# as14120_x31_fpga_cypress.net
KiCad netlist of a schematic drawn in Altium Designer
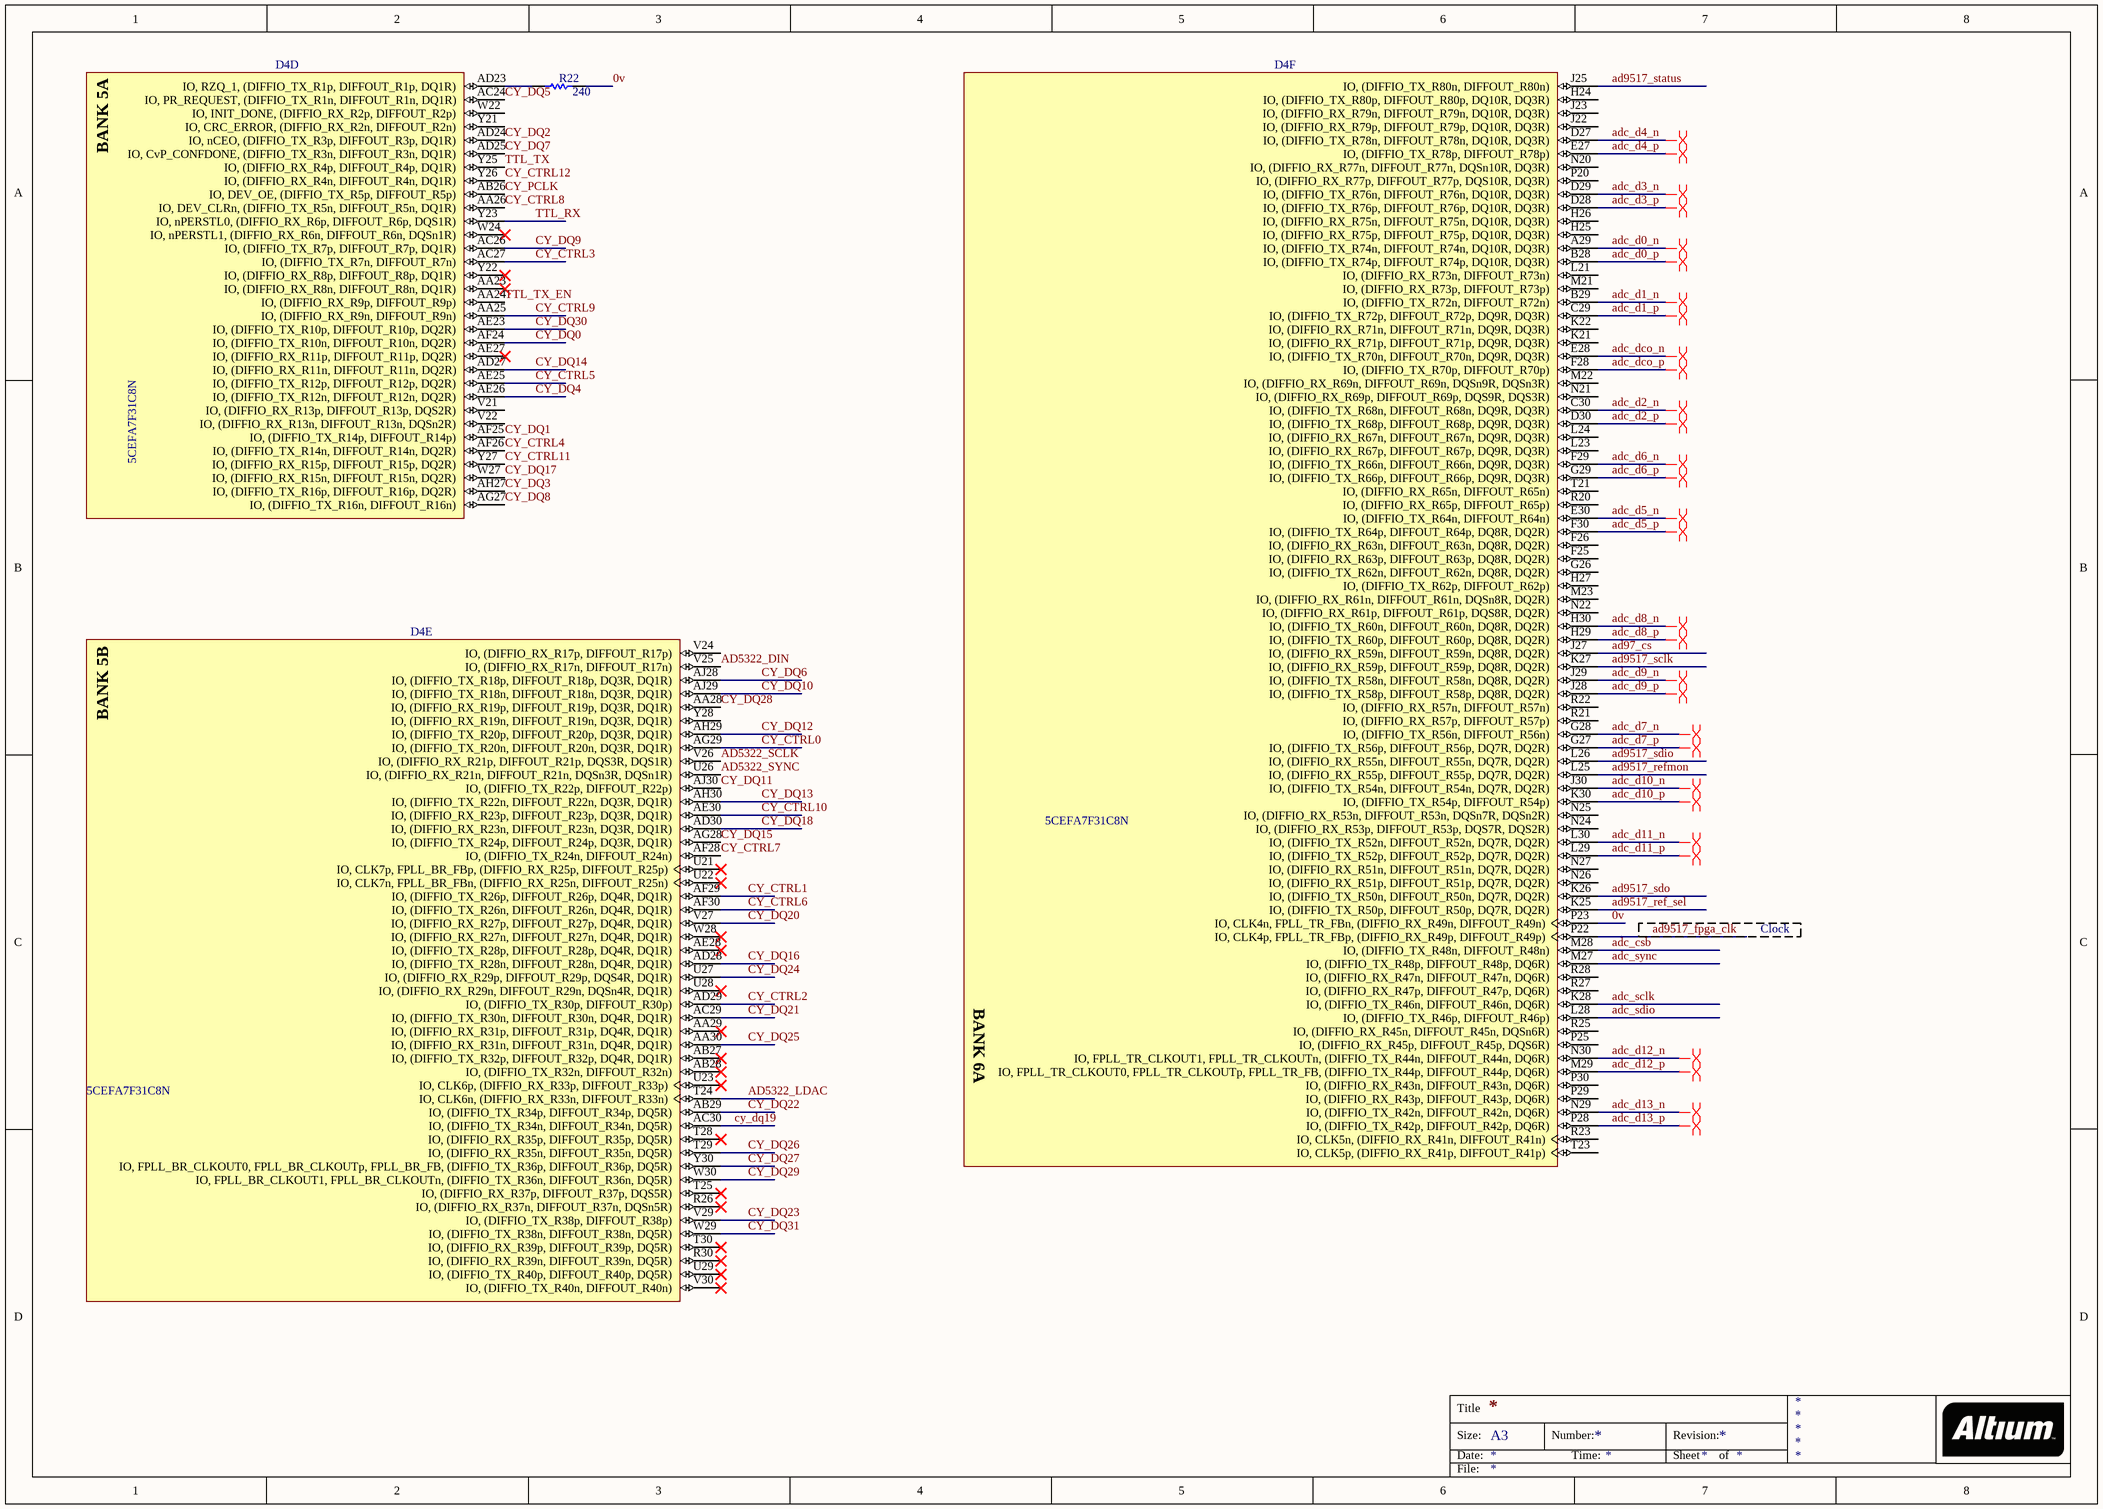
[diagram p0: as14120_x31_fpga_cypress.SchDoc]

(export (version "E")
  (design (tool "Eeschema 10.0.6"))
  (components
    (comp (ref "D4")
      (value "5CEFA7F31C8N")
      (footprint "ALTR-896-FBGA-2000A")
      (fields (field (name "MANUFACTURER") "Altera"))
      (libsource (lib "Altera Cyclone V E") (part "5CEFA7F31C8N"))
    )
    (comp (ref "R22")
      (value "240")
      (footprint "RESC0603(1608)_L")
      (description "1K 0.1W 5% 0603 (1608 Metric)  SMD")
      (fields (field (name "TOLERANCE") "5 %") (field (name "POWER") "0.1 W"))
      (libsource (lib "as14120") (part "RES_0603"))
    )
  )
  (nets
    (net (code "1") (name "/0v") (class "Default")
      (node (ref "D4") (pin "P23") (pinfunction "IO,_CLK4n,_FPLL_TR_FBn,_(DIFFIO_RX_R49n,_DIFFOUT_R49n)_P23") (pintype "bidirectional"))
      (node (ref "R22") (pin "2") (pinfunction "2_2") (pintype "passive"))
    )
    (net (code "2") (name "/AD5322_DIN") (class "Default")
      (node (ref "D4") (pin "V25") (pinfunction "IO,_(DIFFIO_RX_R17n,_DIFFOUT_R17n)_V25") (pintype "bidirectional"))
    )
    (net (code "3") (name "/AD5322_LDAC") (class "Default")
      (node (ref "D4") (pin "T24") (pinfunction "IO,_CLK6n,_(DIFFIO_RX_R33n,_DIFFOUT_R33n)_T24") (pintype "bidirectional"))
    )
    (net (code "4") (name "/AD5322_SCLK") (class "Default")
      (node (ref "D4") (pin "V26") (pinfunction "IO,_(DIFFIO_RX_R21p,_DIFFOUT_R21p,_DQS3R,_DQS1R)_V26") (pintype "bidirectional"))
    )
    (net (code "5") (name "/AD5322_SYNC") (class "Default")
      (node (ref "D4") (pin "U26") (pinfunction "IO,_(DIFFIO_RX_R21n,_DIFFOUT_R21n,_DQSn3R,_DQSn1R)_U26") (pintype "bidirectional"))
    )
    (net (code "6") (name "/CY_CTRL0") (class "Default")
      (node (ref "D4") (pin "AG29") (pinfunction "IO,_(DIFFIO_TX_R20n,_DIFFOUT_R20n,_DQ3R,_DQ1R)_AG29") (pintype "bidirectional"))
    )
    (net (code "7") (name "/CY_CTRL1") (class "Default")
      (node (ref "D4") (pin "AF29") (pinfunction "IO,_(DIFFIO_TX_R26p,_DIFFOUT_R26p,_DQ4R,_DQ1R)_AF29") (pintype "bidirectional"))
    )
    (net (code "8") (name "/CY_CTRL2") (class "Default")
      (node (ref "D4") (pin "AD29") (pinfunction "IO,_(DIFFIO_TX_R30p,_DIFFOUT_R30p)_AD29") (pintype "bidirectional"))
    )
    (net (code "9") (name "/CY_CTRL3") (class "Default")
      (node (ref "D4") (pin "AC27") (pinfunction "IO,_(DIFFIO_TX_R7n,_DIFFOUT_R7n)_AC27") (pintype "bidirectional"))
    )
    (net (code "10") (name "/CY_CTRL4") (class "Default")
      (node (ref "D4") (pin "AF26") (pinfunction "IO,_(DIFFIO_TX_R14n,_DIFFOUT_R14n,_DQ2R)_AF26") (pintype "bidirectional"))
    )
    (net (code "11") (name "/CY_CTRL5") (class "Default")
      (node (ref "D4") (pin "AE25") (pinfunction "IO,_(DIFFIO_TX_R12p,_DIFFOUT_R12p,_DQ2R)_AE25") (pintype "bidirectional"))
    )
    (net (code "12") (name "/CY_CTRL6") (class "Default")
      (node (ref "D4") (pin "AF30") (pinfunction "IO,_(DIFFIO_TX_R26n,_DIFFOUT_R26n,_DQ4R,_DQ1R)_AF30") (pintype "bidirectional"))
    )
    (net (code "13") (name "/CY_CTRL7") (class "Default")
      (node (ref "D4") (pin "AF28") (pinfunction "IO,_(DIFFIO_TX_R24n,_DIFFOUT_R24n)_AF28") (pintype "bidirectional"))
    )
    (net (code "14") (name "/CY_CTRL8") (class "Default")
      (node (ref "D4") (pin "AA26") (pinfunction "IO,_DEV_CLRn,_(DIFFIO_TX_R5n,_DIFFOUT_R5n,_DQ1R)_AA26") (pintype "bidirectional"))
    )
    (net (code "15") (name "/CY_CTRL9") (class "Default")
      (node (ref "D4") (pin "AA25") (pinfunction "IO,_(DIFFIO_RX_R9n,_DIFFOUT_R9n)_AA25") (pintype "bidirectional"))
    )
    (net (code "16") (name "/CY_CTRL10") (class "Default")
      (node (ref "D4") (pin "AE30") (pinfunction "IO,_(DIFFIO_RX_R23p,_DIFFOUT_R23p,_DQ3R,_DQ1R)_AE30") (pintype "bidirectional"))
    )
    (net (code "17") (name "/CY_CTRL11") (class "Default")
      (node (ref "D4") (pin "Y27") (pinfunction "IO,_(DIFFIO_RX_R15p,_DIFFOUT_R15p,_DQ2R)_Y27") (pintype "bidirectional"))
    )
    (net (code "18") (name "/CY_CTRL12") (class "Default")
      (node (ref "D4") (pin "Y26") (pinfunction "IO,_(DIFFIO_RX_R4n,_DIFFOUT_R4n,_DQ1R)_Y26") (pintype "bidirectional"))
    )
    (net (code "19") (name "/CY_DQ0") (class "Default")
      (node (ref "D4") (pin "AF24") (pinfunction "IO,_(DIFFIO_TX_R10n,_DIFFOUT_R10n,_DQ2R)_AF24") (pintype "bidirectional"))
    )
    (net (code "20") (name "/CY_DQ1") (class "Default")
      (node (ref "D4") (pin "AF25") (pinfunction "IO,_(DIFFIO_TX_R14p,_DIFFOUT_R14p)_AF25") (pintype "bidirectional"))
    )
    (net (code "21") (name "/CY_DQ2") (class "Default")
      (node (ref "D4") (pin "AD24") (pinfunction "IO,_nCEO,_(DIFFIO_TX_R3p,_DIFFOUT_R3p,_DQ1R)_AD24") (pintype "bidirectional"))
    )
    (net (code "22") (name "/CY_DQ3") (class "Default")
      (node (ref "D4") (pin "AH27") (pinfunction "IO,_(DIFFIO_TX_R16p,_DIFFOUT_R16p,_DQ2R)_AH27") (pintype "bidirectional"))
    )
    (net (code "23") (name "/CY_DQ4") (class "Default")
      (node (ref "D4") (pin "AE26") (pinfunction "IO,_(DIFFIO_TX_R12n,_DIFFOUT_R12n,_DQ2R)_AE26") (pintype "bidirectional"))
    )
    (net (code "24") (name "/CY_DQ5") (class "Default")
      (node (ref "D4") (pin "AC24") (pinfunction "IO,_PR_REQUEST,_(DIFFIO_TX_R1n,_DIFFOUT_R1n,_DQ1R)_AC24") (pintype "bidirectional"))
    )
    (net (code "25") (name "/CY_DQ6") (class "Default")
      (node (ref "D4") (pin "AJ28") (pinfunction "IO,_(DIFFIO_TX_R18p,_DIFFOUT_R18p,_DQ3R,_DQ1R)_AJ28") (pintype "bidirectional"))
    )
    (net (code "26") (name "/CY_DQ7") (class "Default")
      (node (ref "D4") (pin "AD25") (pinfunction "IO,_CvP_CONFDONE,_(DIFFIO_TX_R3n,_DIFFOUT_R3n,_DQ1R)_AD25") (pintype "bidirectional"))
    )
    (net (code "27") (name "/CY_DQ8") (class "Default")
      (node (ref "D4") (pin "AG27") (pinfunction "IO,_(DIFFIO_TX_R16n,_DIFFOUT_R16n)_AG27") (pintype "bidirectional"))
    )
    (net (code "28") (name "/CY_DQ9") (class "Default")
      (node (ref "D4") (pin "AC26") (pinfunction "IO,_(DIFFIO_TX_R7p,_DIFFOUT_R7p,_DQ1R)_AC26") (pintype "bidirectional"))
    )
    (net (code "29") (name "/CY_DQ10") (class "Default")
      (node (ref "D4") (pin "AJ29") (pinfunction "IO,_(DIFFIO_TX_R18n,_DIFFOUT_R18n,_DQ3R,_DQ1R)_AJ29") (pintype "bidirectional"))
    )
    (net (code "30") (name "/CY_DQ11") (class "Default")
      (node (ref "D4") (pin "AJ30") (pinfunction "IO,_(DIFFIO_TX_R22p,_DIFFOUT_R22p)_AJ30") (pintype "bidirectional"))
    )
    (net (code "31") (name "/CY_DQ12") (class "Default")
      (node (ref "D4") (pin "AH29") (pinfunction "IO,_(DIFFIO_TX_R20p,_DIFFOUT_R20p,_DQ3R,_DQ1R)_AH29") (pintype "bidirectional"))
    )
    (net (code "32") (name "/CY_DQ13") (class "Default")
      (node (ref "D4") (pin "AH30") (pinfunction "IO,_(DIFFIO_TX_R22n,_DIFFOUT_R22n,_DQ3R,_DQ1R)_AH30") (pintype "bidirectional"))
    )
    (net (code "33") (name "/CY_DQ14") (class "Default")
      (node (ref "D4") (pin "AD27") (pinfunction "IO,_(DIFFIO_RX_R11n,_DIFFOUT_R11n,_DQ2R)_AD27") (pintype "bidirectional"))
    )
    (net (code "34") (name "/CY_DQ15") (class "Default")
      (node (ref "D4") (pin "AG28") (pinfunction "IO,_(DIFFIO_TX_R24p,_DIFFOUT_R24p,_DQ3R,_DQ1R)_AG28") (pintype "bidirectional"))
    )
    (net (code "35") (name "/CY_DQ16") (class "Default")
      (node (ref "D4") (pin "AD28") (pinfunction "IO,_(DIFFIO_TX_R28n,_DIFFOUT_R28n,_DQ4R,_DQ1R)_AD28") (pintype "bidirectional"))
    )
    (net (code "36") (name "/CY_DQ17") (class "Default")
      (node (ref "D4") (pin "W27") (pinfunction "IO,_(DIFFIO_RX_R15n,_DIFFOUT_R15n,_DQ2R)_W27") (pintype "bidirectional"))
    )
    (net (code "37") (name "/CY_DQ18") (class "Default")
      (node (ref "D4") (pin "AD30") (pinfunction "IO,_(DIFFIO_RX_R23n,_DIFFOUT_R23n,_DQ3R,_DQ1R)_AD30") (pintype "bidirectional"))
    )
    (net (code "38") (name "/CY_DQ20") (class "Default")
      (node (ref "D4") (pin "V27") (pinfunction "IO,_(DIFFIO_RX_R27p,_DIFFOUT_R27p,_DQ4R,_DQ1R)_V27") (pintype "bidirectional"))
    )
    (net (code "39") (name "/CY_DQ21") (class "Default")
      (node (ref "D4") (pin "AC29") (pinfunction "IO,_(DIFFIO_TX_R30n,_DIFFOUT_R30n,_DQ4R,_DQ1R)_AC29") (pintype "bidirectional"))
    )
    (net (code "40") (name "/CY_DQ22") (class "Default")
      (node (ref "D4") (pin "AB29") (pinfunction "IO,_(DIFFIO_TX_R34p,_DIFFOUT_R34p,_DQ5R)_AB29") (pintype "bidirectional"))
    )
    (net (code "41") (name "/CY_DQ23") (class "Default")
      (node (ref "D4") (pin "V29") (pinfunction "IO,_(DIFFIO_TX_R38p,_DIFFOUT_R38p)_V29") (pintype "bidirectional"))
    )
    (net (code "42") (name "/CY_DQ24") (class "Default")
      (node (ref "D4") (pin "U27") (pinfunction "IO,_(DIFFIO_RX_R29p,_DIFFOUT_R29p,_DQS4R,_DQ1R)_U27") (pintype "bidirectional"))
    )
    (net (code "43") (name "/CY_DQ25") (class "Default")
      (node (ref "D4") (pin "AA30") (pinfunction "IO,_(DIFFIO_RX_R31n,_DIFFOUT_R31n,_DQ4R,_DQ1R)_AA30") (pintype "bidirectional"))
    )
    (net (code "44") (name "/CY_DQ26") (class "Default")
      (node (ref "D4") (pin "T29") (pinfunction "IO,_(DIFFIO_RX_R35n,_DIFFOUT_R35n,_DQ5R)_T29") (pintype "bidirectional"))
    )
    (net (code "45") (name "/CY_DQ27") (class "Default")
      (node (ref "D4") (pin "Y30") (pinfunction "IO,_FPLL_BR_CLKOUT0,_FPLL_BR_CLKOUTp,_FPLL_BR_FB,_(DIFFIO_TX_R36p,_DIFFOUT_R36p,_DQ5R)_Y30") (pintype "bidirectional"))
    )
    (net (code "46") (name "/CY_DQ28") (class "Default")
      (node (ref "D4") (pin "AA28") (pinfunction "IO,_(DIFFIO_RX_R19p,_DIFFOUT_R19p,_DQ3R,_DQ1R)_AA28") (pintype "bidirectional"))
    )
    (net (code "47") (name "/CY_DQ29") (class "Default")
      (node (ref "D4") (pin "W30") (pinfunction "IO,_FPLL_BR_CLKOUT1,_FPLL_BR_CLKOUTn,_(DIFFIO_TX_R36n,_DIFFOUT_R36n,_DQ5R)_W30") (pintype "bidirectional"))
    )
    (net (code "48") (name "/CY_DQ30") (class "Default")
      (node (ref "D4") (pin "AE23") (pinfunction "IO,_(DIFFIO_TX_R10p,_DIFFOUT_R10p,_DQ2R)_AE23") (pintype "bidirectional"))
    )
    (net (code "49") (name "/CY_DQ31") (class "Default")
      (node (ref "D4") (pin "W29") (pinfunction "IO,_(DIFFIO_TX_R38n,_DIFFOUT_R38n,_DQ5R)_W29") (pintype "bidirectional"))
    )
    (net (code "50") (name "/CY_PCLK") (class "Default")
      (node (ref "D4") (pin "AB26") (pinfunction "IO,_DEV_OE,_(DIFFIO_TX_R5p,_DIFFOUT_R5p)_AB26") (pintype "bidirectional"))
    )
    (net (code "51") (name "/TTL_RX") (class "Default")
      (node (ref "D4") (pin "Y23") (pinfunction "IO,_nPERSTL0,_(DIFFIO_RX_R6p,_DIFFOUT_R6p,_DQS1R)_Y23") (pintype "bidirectional"))
    )
    (net (code "52") (name "/TTL_TX") (class "Default")
      (node (ref "D4") (pin "Y25") (pinfunction "IO,_(DIFFIO_RX_R4p,_DIFFOUT_R4p,_DQ1R)_Y25") (pintype "bidirectional"))
    )
    (net (code "53") (name "/TTL_TX_EN") (class "Default")
      (node (ref "D4") (pin "AA24") (pinfunction "IO,_(DIFFIO_RX_R9p,_DIFFOUT_R9p)_AA24") (pintype "bidirectional"))
    )
    (net (code "54") (name "/ad97_cs") (class "Default")
      (node (ref "D4") (pin "J27") (pinfunction "IO,_(DIFFIO_RX_R59n,_DIFFOUT_R59n,_DQ8R,_DQ2R)_J27") (pintype "bidirectional"))
    )
    (net (code "55") (name "/ad9517_fpga_clk") (class "Default")
      (node (ref "D4") (pin "P22") (pinfunction "IO,_CLK4p,_FPLL_TR_FBp,_(DIFFIO_RX_R49p,_DIFFOUT_R49p)_P22") (pintype "bidirectional"))
    )
    (net (code "56") (name "/ad9517_ref_sel") (class "Default")
      (node (ref "D4") (pin "K25") (pinfunction "IO,_(DIFFIO_TX_R50p,_DIFFOUT_R50p,_DQ7R,_DQ2R)_K25") (pintype "bidirectional"))
    )
    (net (code "57") (name "/ad9517_refmon") (class "Default")
      (node (ref "D4") (pin "L25") (pinfunction "IO,_(DIFFIO_RX_R55p,_DIFFOUT_R55p,_DQ7R,_DQ2R)_L25") (pintype "bidirectional"))
    )
    (net (code "58") (name "/ad9517_sclk") (class "Default")
      (node (ref "D4") (pin "K27") (pinfunction "IO,_(DIFFIO_RX_R59p,_DIFFOUT_R59p,_DQ8R,_DQ2R)_K27") (pintype "bidirectional"))
    )
    (net (code "59") (name "/ad9517_sdio") (class "Default")
      (node (ref "D4") (pin "L26") (pinfunction "IO,_(DIFFIO_RX_R55n,_DIFFOUT_R55n,_DQ7R,_DQ2R)_L26") (pintype "bidirectional"))
    )
    (net (code "60") (name "/ad9517_sdo") (class "Default")
      (node (ref "D4") (pin "K26") (pinfunction "IO,_(DIFFIO_TX_R50n,_DIFFOUT_R50n,_DQ7R,_DQ2R)_K26") (pintype "bidirectional"))
    )
    (net (code "61") (name "/ad9517_status") (class "Default")
      (node (ref "D4") (pin "J25") (pinfunction "IO,_(DIFFIO_TX_R80n,_DIFFOUT_R80n)_J25") (pintype "bidirectional"))
    )
    (net (code "62") (name "/adc_csb") (class "Default")
      (node (ref "D4") (pin "M28") (pinfunction "IO,_(DIFFIO_TX_R48n,_DIFFOUT_R48n)_M28") (pintype "bidirectional"))
    )
    (net (code "63") (name "/adc_d0_n") (class "Default")
      (node (ref "D4") (pin "A29") (pinfunction "IO,_(DIFFIO_TX_R74n,_DIFFOUT_R74n,_DQ10R,_DQ3R)_A29") (pintype "bidirectional"))
    )
    (net (code "64") (name "/adc_d0_p") (class "Default")
      (node (ref "D4") (pin "B28") (pinfunction "IO,_(DIFFIO_TX_R74p,_DIFFOUT_R74p,_DQ10R,_DQ3R)_B28") (pintype "bidirectional"))
    )
    (net (code "65") (name "/adc_d1_n") (class "Default")
      (node (ref "D4") (pin "B29") (pinfunction "IO,_(DIFFIO_TX_R72n,_DIFFOUT_R72n)_B29") (pintype "bidirectional"))
    )
    (net (code "66") (name "/adc_d1_p") (class "Default")
      (node (ref "D4") (pin "C29") (pinfunction "IO,_(DIFFIO_TX_R72p,_DIFFOUT_R72p,_DQ9R,_DQ3R)_C29") (pintype "bidirectional"))
    )
    (net (code "67") (name "/adc_d2_n") (class "Default")
      (node (ref "D4") (pin "C30") (pinfunction "IO,_(DIFFIO_TX_R68n,_DIFFOUT_R68n,_DQ9R,_DQ3R)_C30") (pintype "bidirectional"))
    )
    (net (code "68") (name "/adc_d2_p") (class "Default")
      (node (ref "D4") (pin "D30") (pinfunction "IO,_(DIFFIO_TX_R68p,_DIFFOUT_R68p,_DQ9R,_DQ3R)_D30") (pintype "bidirectional"))
    )
    (net (code "69") (name "/adc_d3_n") (class "Default")
      (node (ref "D4") (pin "D29") (pinfunction "IO,_(DIFFIO_TX_R76n,_DIFFOUT_R76n,_DQ10R,_DQ3R)_D29") (pintype "bidirectional"))
    )
    (net (code "70") (name "/adc_d3_p") (class "Default")
      (node (ref "D4") (pin "D28") (pinfunction "IO,_(DIFFIO_TX_R76p,_DIFFOUT_R76p,_DQ10R,_DQ3R)_D28") (pintype "bidirectional"))
    )
    (net (code "71") (name "/adc_d4_n") (class "Default")
      (node (ref "D4") (pin "D27") (pinfunction "IO,_(DIFFIO_TX_R78n,_DIFFOUT_R78n,_DQ10R,_DQ3R)_D27") (pintype "bidirectional"))
    )
    (net (code "72") (name "/adc_d4_p") (class "Default")
      (node (ref "D4") (pin "E27") (pinfunction "IO,_(DIFFIO_TX_R78p,_DIFFOUT_R78p)_E27") (pintype "bidirectional"))
    )
    (net (code "73") (name "/adc_d5_n") (class "Default")
      (node (ref "D4") (pin "E30") (pinfunction "IO,_(DIFFIO_TX_R64n,_DIFFOUT_R64n)_E30") (pintype "bidirectional"))
    )
    (net (code "74") (name "/adc_d5_p") (class "Default")
      (node (ref "D4") (pin "F30") (pinfunction "IO,_(DIFFIO_TX_R64p,_DIFFOUT_R64p,_DQ8R,_DQ2R)_F30") (pintype "bidirectional"))
    )
    (net (code "75") (name "/adc_d6_n") (class "Default")
      (node (ref "D4") (pin "F29") (pinfunction "IO,_(DIFFIO_TX_R66n,_DIFFOUT_R66n,_DQ9R,_DQ3R)_F29") (pintype "bidirectional"))
    )
    (net (code "76") (name "/adc_d6_p") (class "Default")
      (node (ref "D4") (pin "G29") (pinfunction "IO,_(DIFFIO_TX_R66p,_DIFFOUT_R66p,_DQ9R,_DQ3R)_G29") (pintype "bidirectional"))
    )
    (net (code "77") (name "/adc_d7_n") (class "Default")
      (node (ref "D4") (pin "G28") (pinfunction "IO,_(DIFFIO_TX_R56n,_DIFFOUT_R56n)_G28") (pintype "bidirectional"))
    )
    (net (code "78") (name "/adc_d7_p") (class "Default")
      (node (ref "D4") (pin "G27") (pinfunction "IO,_(DIFFIO_TX_R56p,_DIFFOUT_R56p,_DQ7R,_DQ2R)_G27") (pintype "bidirectional"))
    )
    (net (code "79") (name "/adc_d8_n") (class "Default")
      (node (ref "D4") (pin "H30") (pinfunction "IO,_(DIFFIO_TX_R60n,_DIFFOUT_R60n,_DQ8R,_DQ2R)_H30") (pintype "bidirectional"))
    )
    (net (code "80") (name "/adc_d8_p") (class "Default")
      (node (ref "D4") (pin "H29") (pinfunction "IO,_(DIFFIO_TX_R60p,_DIFFOUT_R60p,_DQ8R,_DQ2R)_H29") (pintype "bidirectional"))
    )
    (net (code "81") (name "/adc_d9_n") (class "Default")
      (node (ref "D4") (pin "J29") (pinfunction "IO,_(DIFFIO_TX_R58n,_DIFFOUT_R58n,_DQ8R,_DQ2R)_J29") (pintype "bidirectional"))
    )
    (net (code "82") (name "/adc_d9_p") (class "Default")
      (node (ref "D4") (pin "J28") (pinfunction "IO,_(DIFFIO_TX_R58p,_DIFFOUT_R58p,_DQ8R,_DQ2R)_J28") (pintype "bidirectional"))
    )
    (net (code "83") (name "/adc_d10_n") (class "Default")
      (node (ref "D4") (pin "J30") (pinfunction "IO,_(DIFFIO_TX_R54n,_DIFFOUT_R54n,_DQ7R,_DQ2R)_J30") (pintype "bidirectional"))
    )
    (net (code "84") (name "/adc_d10_p") (class "Default")
      (node (ref "D4") (pin "K30") (pinfunction "IO,_(DIFFIO_TX_R54p,_DIFFOUT_R54p)_K30") (pintype "bidirectional"))
    )
    (net (code "85") (name "/adc_d11_n") (class "Default")
      (node (ref "D4") (pin "L30") (pinfunction "IO,_(DIFFIO_TX_R52n,_DIFFOUT_R52n,_DQ7R,_DQ2R)_L30") (pintype "bidirectional"))
    )
    (net (code "86") (name "/adc_d11_p") (class "Default")
      (node (ref "D4") (pin "L29") (pinfunction "IO,_(DIFFIO_TX_R52p,_DIFFOUT_R52p,_DQ7R,_DQ2R)_L29") (pintype "bidirectional"))
    )
    (net (code "87") (name "/adc_d12_n") (class "Default")
      (node (ref "D4") (pin "N30") (pinfunction "IO,_FPLL_TR_CLKOUT1,_FPLL_TR_CLKOUTn,_(DIFFIO_TX_R44n,_DIFFOUT_R44n,_DQ6R)_N30") (pintype "bidirectional"))
    )
    (net (code "88") (name "/adc_d12_p") (class "Default")
      (node (ref "D4") (pin "M29") (pinfunction "IO,_FPLL_TR_CLKOUT0,_FPLL_TR_CLKOUTp,_FPLL_TR_FB,_(DIFFIO_TX_R44p,_DIFFOUT_R44p,_DQ6R)_M29") (pintype "bidirectional"))
    )
    (net (code "89") (name "/adc_d13_n") (class "Default")
      (node (ref "D4") (pin "N29") (pinfunction "IO,_(DIFFIO_TX_R42n,_DIFFOUT_R42n,_DQ6R)_N29") (pintype "bidirectional"))
    )
    (net (code "90") (name "/adc_d13_p") (class "Default")
      (node (ref "D4") (pin "P28") (pinfunction "IO,_(DIFFIO_TX_R42p,_DIFFOUT_R42p,_DQ6R)_P28") (pintype "bidirectional"))
    )
    (net (code "91") (name "/adc_dco_n") (class "Default")
      (node (ref "D4") (pin "E28") (pinfunction "IO,_(DIFFIO_TX_R70n,_DIFFOUT_R70n,_DQ9R,_DQ3R)_E28") (pintype "bidirectional"))
    )
    (net (code "92") (name "/adc_dco_p") (class "Default")
      (node (ref "D4") (pin "F28") (pinfunction "IO,_(DIFFIO_TX_R70p,_DIFFOUT_R70p)_F28") (pintype "bidirectional"))
    )
    (net (code "93") (name "/adc_sclk") (class "Default")
      (node (ref "D4") (pin "K28") (pinfunction "IO,_(DIFFIO_TX_R46n,_DIFFOUT_R46n,_DQ6R)_K28") (pintype "bidirectional"))
    )
    (net (code "94") (name "/adc_sdio") (class "Default")
      (node (ref "D4") (pin "L28") (pinfunction "IO,_(DIFFIO_TX_R46p,_DIFFOUT_R46p)_L28") (pintype "bidirectional"))
    )
    (net (code "95") (name "/adc_sync") (class "Default")
      (node (ref "D4") (pin "M27") (pinfunction "IO,_(DIFFIO_TX_R48p,_DIFFOUT_R48p,_DQ6R)_M27") (pintype "bidirectional"))
    )
    (net (code "96") (name "/cy_dq19") (class "Default")
      (node (ref "D4") (pin "AC30") (pinfunction "IO,_(DIFFIO_TX_R34n,_DIFFOUT_R34n,_DQ5R)_AC30") (pintype "bidirectional"))
    )
    (net (code "97") (name "Net-(D4D-IO,_RZQ_1,_(DIFFIO_TX_R1p,_DIFFOUT_R1p,_DQ1R))") (class "Default")
      (node (ref "D4") (pin "AD23") (pinfunction "IO,_RZQ_1,_(DIFFIO_TX_R1p,_DIFFOUT_R1p,_DQ1R)_AD23") (pintype "bidirectional"))
      (node (ref "R22") (pin "1") (pinfunction "1_1") (pintype "passive"))
    )
    (net (code "98") (name "unconnected-(D4D-IO,_(DIFFIO_RX_R8n,_DIFFOUT_R8n,_DQ1R)-PadAA23)") (class "Default")
      (node (ref "D4") (pin "AA23") (pinfunction "IO,_(DIFFIO_RX_R8n,_DIFFOUT_R8n,_DQ1R)_AA23") (pintype "bidirectional+no_connect"))
    )
    (net (code "99") (name "unconnected-(D4D-IO,_(DIFFIO_RX_R8p,_DIFFOUT_R8p,_DQ1R)-PadY22)") (class "Default")
      (node (ref "D4") (pin "Y22") (pinfunction "IO,_(DIFFIO_RX_R8p,_DIFFOUT_R8p,_DQ1R)_Y22") (pintype "bidirectional+no_connect"))
    )
    (net (code "100") (name "unconnected-(D4D-IO,_(DIFFIO_RX_R11p,_DIFFOUT_R11p,_DQ2R)-PadAE27)") (class "Default")
      (node (ref "D4") (pin "AE27") (pinfunction "IO,_(DIFFIO_RX_R11p,_DIFFOUT_R11p,_DQ2R)_AE27") (pintype "bidirectional+no_connect"))
    )
    (net (code "101") (name "unconnected-(D4D-IO,_(DIFFIO_RX_R13n,_DIFFOUT_R13n,_DQSn2R)-PadV22)") (class "Default")
      (node (ref "D4") (pin "V22") (pinfunction "IO,_(DIFFIO_RX_R13n,_DIFFOUT_R13n,_DQSn2R)_V22") (pintype "bidirectional"))
    )
    (net (code "102") (name "unconnected-(D4D-IO,_(DIFFIO_RX_R13p,_DIFFOUT_R13p,_DQS2R)-PadV21)") (class "Default")
      (node (ref "D4") (pin "V21") (pinfunction "IO,_(DIFFIO_RX_R13p,_DIFFOUT_R13p,_DQS2R)_V21") (pintype "bidirectional"))
    )
    (net (code "103") (name "unconnected-(D4D-IO,_CRC_ERROR,_(DIFFIO_RX_R2n,_DIFFOUT_R2n)-PadY21)") (class "Default")
      (node (ref "D4") (pin "Y21") (pinfunction "IO,_CRC_ERROR,_(DIFFIO_RX_R2n,_DIFFOUT_R2n)_Y21") (pintype "bidirectional"))
    )
    (net (code "104") (name "unconnected-(D4D-IO,_INIT_DONE,_(DIFFIO_RX_R2p,_DIFFOUT_R2p)-PadW22)") (class "Default")
      (node (ref "D4") (pin "W22") (pinfunction "IO,_INIT_DONE,_(DIFFIO_RX_R2p,_DIFFOUT_R2p)_W22") (pintype "bidirectional"))
    )
    (net (code "105") (name "unconnected-(D4D-IO,_nPERSTL1,_(DIFFIO_RX_R6n,_DIFFOUT_R6n,_DQSn1R)-PadW24)") (class "Default")
      (node (ref "D4") (pin "W24") (pinfunction "IO,_nPERSTL1,_(DIFFIO_RX_R6n,_DIFFOUT_R6n,_DQSn1R)_W24") (pintype "bidirectional+no_connect"))
    )
    (net (code "106") (name "unconnected-(D4E-IO,_(DIFFIO_RX_R17p,_DIFFOUT_R17p)-PadV24)") (class "Default")
      (node (ref "D4") (pin "V24") (pinfunction "IO,_(DIFFIO_RX_R17p,_DIFFOUT_R17p)_V24") (pintype "bidirectional"))
    )
    (net (code "107") (name "unconnected-(D4E-IO,_(DIFFIO_RX_R19n,_DIFFOUT_R19n,_DQ3R,_DQ1R)-PadY28)") (class "Default")
      (node (ref "D4") (pin "Y28") (pinfunction "IO,_(DIFFIO_RX_R19n,_DIFFOUT_R19n,_DQ3R,_DQ1R)_Y28") (pintype "bidirectional"))
    )
    (net (code "108") (name "unconnected-(D4E-IO,_(DIFFIO_RX_R27n,_DIFFOUT_R27n,_DQ4R,_DQ1R)-PadW28)") (class "Default")
      (node (ref "D4") (pin "W28") (pinfunction "IO,_(DIFFIO_RX_R27n,_DIFFOUT_R27n,_DQ4R,_DQ1R)_W28") (pintype "bidirectional+no_connect"))
    )
    (net (code "109") (name "unconnected-(D4E-IO,_(DIFFIO_RX_R29n,_DIFFOUT_R29n,_DQSn4R,_DQ1R)-PadU28)") (class "Default")
      (node (ref "D4") (pin "U28") (pinfunction "IO,_(DIFFIO_RX_R29n,_DIFFOUT_R29n,_DQSn4R,_DQ1R)_U28") (pintype "bidirectional+no_connect"))
    )
    (net (code "110") (name "unconnected-(D4E-IO,_(DIFFIO_RX_R31p,_DIFFOUT_R31p,_DQ4R,_DQ1R)-PadAA29)") (class "Default")
      (node (ref "D4") (pin "AA29") (pinfunction "IO,_(DIFFIO_RX_R31p,_DIFFOUT_R31p,_DQ4R,_DQ1R)_AA29") (pintype "bidirectional+no_connect"))
    )
    (net (code "111") (name "unconnected-(D4E-IO,_(DIFFIO_RX_R35p,_DIFFOUT_R35p,_DQ5R)-PadT28)") (class "Default")
      (node (ref "D4") (pin "T28") (pinfunction "IO,_(DIFFIO_RX_R35p,_DIFFOUT_R35p,_DQ5R)_T28") (pintype "bidirectional+no_connect"))
    )
    (net (code "112") (name "unconnected-(D4E-IO,_(DIFFIO_RX_R37n,_DIFFOUT_R37n,_DQSn5R)-PadR26)") (class "Default")
      (node (ref "D4") (pin "R26") (pinfunction "IO,_(DIFFIO_RX_R37n,_DIFFOUT_R37n,_DQSn5R)_R26") (pintype "bidirectional+no_connect"))
    )
    (net (code "113") (name "unconnected-(D4E-IO,_(DIFFIO_RX_R37p,_DIFFOUT_R37p,_DQS5R)-PadT25)") (class "Default")
      (node (ref "D4") (pin "T25") (pinfunction "IO,_(DIFFIO_RX_R37p,_DIFFOUT_R37p,_DQS5R)_T25") (pintype "bidirectional+no_connect"))
    )
    (net (code "114") (name "unconnected-(D4E-IO,_(DIFFIO_RX_R39n,_DIFFOUT_R39n,_DQ5R)-PadR30)") (class "Default")
      (node (ref "D4") (pin "R30") (pinfunction "IO,_(DIFFIO_RX_R39n,_DIFFOUT_R39n,_DQ5R)_R30") (pintype "bidirectional+no_connect"))
    )
    (net (code "115") (name "unconnected-(D4E-IO,_(DIFFIO_RX_R39p,_DIFFOUT_R39p,_DQ5R)-PadT30)") (class "Default")
      (node (ref "D4") (pin "T30") (pinfunction "IO,_(DIFFIO_RX_R39p,_DIFFOUT_R39p,_DQ5R)_T30") (pintype "bidirectional+no_connect"))
    )
    (net (code "116") (name "unconnected-(D4E-IO,_(DIFFIO_TX_R28p,_DIFFOUT_R28p,_DQ4R,_DQ1R)-PadAE28)") (class "Default")
      (node (ref "D4") (pin "AE28") (pinfunction "IO,_(DIFFIO_TX_R28p,_DIFFOUT_R28p,_DQ4R,_DQ1R)_AE28") (pintype "bidirectional+no_connect"))
    )
    (net (code "117") (name "unconnected-(D4E-IO,_(DIFFIO_TX_R32n,_DIFFOUT_R32n)-PadAB28)") (class "Default")
      (node (ref "D4") (pin "AB28") (pinfunction "IO,_(DIFFIO_TX_R32n,_DIFFOUT_R32n)_AB28") (pintype "bidirectional+no_connect"))
    )
    (net (code "118") (name "unconnected-(D4E-IO,_(DIFFIO_TX_R32p,_DIFFOUT_R32p,_DQ4R,_DQ1R)-PadAB27)") (class "Default")
      (node (ref "D4") (pin "AB27") (pinfunction "IO,_(DIFFIO_TX_R32p,_DIFFOUT_R32p,_DQ4R,_DQ1R)_AB27") (pintype "bidirectional+no_connect"))
    )
    (net (code "119") (name "unconnected-(D4E-IO,_(DIFFIO_TX_R40n,_DIFFOUT_R40n)-PadV30)") (class "Default")
      (node (ref "D4") (pin "V30") (pinfunction "IO,_(DIFFIO_TX_R40n,_DIFFOUT_R40n)_V30") (pintype "bidirectional+no_connect"))
    )
    (net (code "120") (name "unconnected-(D4E-IO,_(DIFFIO_TX_R40p,_DIFFOUT_R40p,_DQ5R)-PadU29)") (class "Default")
      (node (ref "D4") (pin "U29") (pinfunction "IO,_(DIFFIO_TX_R40p,_DIFFOUT_R40p,_DQ5R)_U29") (pintype "bidirectional+no_connect"))
    )
    (net (code "121") (name "unconnected-(D4E-IO,_CLK6p,_(DIFFIO_RX_R33p,_DIFFOUT_R33p)-PadU23)") (class "Default")
      (node (ref "D4") (pin "U23") (pinfunction "IO,_CLK6p,_(DIFFIO_RX_R33p,_DIFFOUT_R33p)_U23") (pintype "bidirectional+no_connect"))
    )
    (net (code "122") (name "unconnected-(D4E-IO,_CLK7n,_FPLL_BR_FBn,_(DIFFIO_RX_R25n,_DIFFOUT_R25n)-PadU22)") (class "Default")
      (node (ref "D4") (pin "U22") (pinfunction "IO,_CLK7n,_FPLL_BR_FBn,_(DIFFIO_RX_R25n,_DIFFOUT_R25n)_U22") (pintype "bidirectional+no_connect"))
    )
    (net (code "123") (name "unconnected-(D4E-IO,_CLK7p,_FPLL_BR_FBp,_(DIFFIO_RX_R25p,_DIFFOUT_R25p)-PadU21)") (class "Default")
      (node (ref "D4") (pin "U21") (pinfunction "IO,_CLK7p,_FPLL_BR_FBp,_(DIFFIO_RX_R25p,_DIFFOUT_R25p)_U21") (pintype "bidirectional+no_connect"))
    )
    (net (code "124") (name "unconnected-(D4F-IO,_(DIFFIO_RX_R43n,_DIFFOUT_R43n,_DQ6R)-PadP30)") (class "Default")
      (node (ref "D4") (pin "P30") (pinfunction "IO,_(DIFFIO_RX_R43n,_DIFFOUT_R43n,_DQ6R)_P30") (pintype "bidirectional"))
    )
    (net (code "125") (name "unconnected-(D4F-IO,_(DIFFIO_RX_R43p,_DIFFOUT_R43p,_DQ6R)-PadP29)") (class "Default")
      (node (ref "D4") (pin "P29") (pinfunction "IO,_(DIFFIO_RX_R43p,_DIFFOUT_R43p,_DQ6R)_P29") (pintype "bidirectional"))
    )
    (net (code "126") (name "unconnected-(D4F-IO,_(DIFFIO_RX_R45n,_DIFFOUT_R45n,_DQSn6R)-PadR25)") (class "Default")
      (node (ref "D4") (pin "R25") (pinfunction "IO,_(DIFFIO_RX_R45n,_DIFFOUT_R45n,_DQSn6R)_R25") (pintype "bidirectional"))
    )
    (net (code "127") (name "unconnected-(D4F-IO,_(DIFFIO_RX_R45p,_DIFFOUT_R45p,_DQS6R)-PadP25)") (class "Default")
      (node (ref "D4") (pin "P25") (pinfunction "IO,_(DIFFIO_RX_R45p,_DIFFOUT_R45p,_DQS6R)_P25") (pintype "bidirectional"))
    )
    (net (code "128") (name "unconnected-(D4F-IO,_(DIFFIO_RX_R47n,_DIFFOUT_R47n,_DQ6R)-PadR28)") (class "Default")
      (node (ref "D4") (pin "R28") (pinfunction "IO,_(DIFFIO_RX_R47n,_DIFFOUT_R47n,_DQ6R)_R28") (pintype "bidirectional"))
    )
    (net (code "129") (name "unconnected-(D4F-IO,_(DIFFIO_RX_R47p,_DIFFOUT_R47p,_DQ6R)-PadR27)") (class "Default")
      (node (ref "D4") (pin "R27") (pinfunction "IO,_(DIFFIO_RX_R47p,_DIFFOUT_R47p,_DQ6R)_R27") (pintype "bidirectional"))
    )
    (net (code "130") (name "unconnected-(D4F-IO,_(DIFFIO_RX_R51n,_DIFFOUT_R51n,_DQ7R,_DQ2R)-PadN27)") (class "Default")
      (node (ref "D4") (pin "N27") (pinfunction "IO,_(DIFFIO_RX_R51n,_DIFFOUT_R51n,_DQ7R,_DQ2R)_N27") (pintype "bidirectional"))
    )
    (net (code "131") (name "unconnected-(D4F-IO,_(DIFFIO_RX_R51p,_DIFFOUT_R51p,_DQ7R,_DQ2R)-PadN26)") (class "Default")
      (node (ref "D4") (pin "N26") (pinfunction "IO,_(DIFFIO_RX_R51p,_DIFFOUT_R51p,_DQ7R,_DQ2R)_N26") (pintype "bidirectional"))
    )
    (net (code "132") (name "unconnected-(D4F-IO,_(DIFFIO_RX_R53n,_DIFFOUT_R53n,_DQSn7R,_DQSn2R)-PadN25)") (class "Default")
      (node (ref "D4") (pin "N25") (pinfunction "IO,_(DIFFIO_RX_R53n,_DIFFOUT_R53n,_DQSn7R,_DQSn2R)_N25") (pintype "bidirectional"))
    )
    (net (code "133") (name "unconnected-(D4F-IO,_(DIFFIO_RX_R53p,_DIFFOUT_R53p,_DQS7R,_DQS2R)-PadN24)") (class "Default")
      (node (ref "D4") (pin "N24") (pinfunction "IO,_(DIFFIO_RX_R53p,_DIFFOUT_R53p,_DQS7R,_DQS2R)_N24") (pintype "bidirectional"))
    )
    (net (code "134") (name "unconnected-(D4F-IO,_(DIFFIO_RX_R57n,_DIFFOUT_R57n)-PadR22)") (class "Default")
      (node (ref "D4") (pin "R22") (pinfunction "IO,_(DIFFIO_RX_R57n,_DIFFOUT_R57n)_R22") (pintype "bidirectional"))
    )
    (net (code "135") (name "unconnected-(D4F-IO,_(DIFFIO_RX_R57p,_DIFFOUT_R57p)-PadR21)") (class "Default")
      (node (ref "D4") (pin "R21") (pinfunction "IO,_(DIFFIO_RX_R57p,_DIFFOUT_R57p)_R21") (pintype "bidirectional"))
    )
    (net (code "136") (name "unconnected-(D4F-IO,_(DIFFIO_RX_R61n,_DIFFOUT_R61n,_DQSn8R,_DQ2R)-PadM23)") (class "Default")
      (node (ref "D4") (pin "M23") (pinfunction "IO,_(DIFFIO_RX_R61n,_DIFFOUT_R61n,_DQSn8R,_DQ2R)_M23") (pintype "bidirectional"))
    )
    (net (code "137") (name "unconnected-(D4F-IO,_(DIFFIO_RX_R61p,_DIFFOUT_R61p,_DQS8R,_DQ2R)-PadN22)") (class "Default")
      (node (ref "D4") (pin "N22") (pinfunction "IO,_(DIFFIO_RX_R61p,_DIFFOUT_R61p,_DQS8R,_DQ2R)_N22") (pintype "bidirectional"))
    )
    (net (code "138") (name "unconnected-(D4F-IO,_(DIFFIO_RX_R63n,_DIFFOUT_R63n,_DQ8R,_DQ2R)-PadF26)") (class "Default")
      (node (ref "D4") (pin "F26") (pinfunction "IO,_(DIFFIO_RX_R63n,_DIFFOUT_R63n,_DQ8R,_DQ2R)_F26") (pintype "bidirectional"))
    )
    (net (code "139") (name "unconnected-(D4F-IO,_(DIFFIO_RX_R63p,_DIFFOUT_R63p,_DQ8R,_DQ2R)-PadF25)") (class "Default")
      (node (ref "D4") (pin "F25") (pinfunction "IO,_(DIFFIO_RX_R63p,_DIFFOUT_R63p,_DQ8R,_DQ2R)_F25") (pintype "bidirectional"))
    )
    (net (code "140") (name "unconnected-(D4F-IO,_(DIFFIO_RX_R65n,_DIFFOUT_R65n)-PadT21)") (class "Default")
      (node (ref "D4") (pin "T21") (pinfunction "IO,_(DIFFIO_RX_R65n,_DIFFOUT_R65n)_T21") (pintype "bidirectional"))
    )
    (net (code "141") (name "unconnected-(D4F-IO,_(DIFFIO_RX_R65p,_DIFFOUT_R65p)-PadR20)") (class "Default")
      (node (ref "D4") (pin "R20") (pinfunction "IO,_(DIFFIO_RX_R65p,_DIFFOUT_R65p)_R20") (pintype "bidirectional"))
    )
    (net (code "142") (name "unconnected-(D4F-IO,_(DIFFIO_RX_R67n,_DIFFOUT_R67n,_DQ9R,_DQ3R)-PadL24)") (class "Default")
      (node (ref "D4") (pin "L24") (pinfunction "IO,_(DIFFIO_RX_R67n,_DIFFOUT_R67n,_DQ9R,_DQ3R)_L24") (pintype "bidirectional"))
    )
    (net (code "143") (name "unconnected-(D4F-IO,_(DIFFIO_RX_R67p,_DIFFOUT_R67p,_DQ9R,_DQ3R)-PadL23)") (class "Default")
      (node (ref "D4") (pin "L23") (pinfunction "IO,_(DIFFIO_RX_R67p,_DIFFOUT_R67p,_DQ9R,_DQ3R)_L23") (pintype "bidirectional"))
    )
    (net (code "144") (name "unconnected-(D4F-IO,_(DIFFIO_RX_R69n,_DIFFOUT_R69n,_DQSn9R,_DQSn3R)-PadM22)") (class "Default")
      (node (ref "D4") (pin "M22") (pinfunction "IO,_(DIFFIO_RX_R69n,_DIFFOUT_R69n,_DQSn9R,_DQSn3R)_M22") (pintype "bidirectional"))
    )
    (net (code "145") (name "unconnected-(D4F-IO,_(DIFFIO_RX_R69p,_DIFFOUT_R69p,_DQS9R,_DQS3R)-PadN21)") (class "Default")
      (node (ref "D4") (pin "N21") (pinfunction "IO,_(DIFFIO_RX_R69p,_DIFFOUT_R69p,_DQS9R,_DQS3R)_N21") (pintype "bidirectional"))
    )
    (net (code "146") (name "unconnected-(D4F-IO,_(DIFFIO_RX_R71n,_DIFFOUT_R71n,_DQ9R,_DQ3R)-PadK22)") (class "Default")
      (node (ref "D4") (pin "K22") (pinfunction "IO,_(DIFFIO_RX_R71n,_DIFFOUT_R71n,_DQ9R,_DQ3R)_K22") (pintype "bidirectional"))
    )
    (net (code "147") (name "unconnected-(D4F-IO,_(DIFFIO_RX_R71p,_DIFFOUT_R71p,_DQ9R,_DQ3R)-PadK21)") (class "Default")
      (node (ref "D4") (pin "K21") (pinfunction "IO,_(DIFFIO_RX_R71p,_DIFFOUT_R71p,_DQ9R,_DQ3R)_K21") (pintype "bidirectional"))
    )
    (net (code "148") (name "unconnected-(D4F-IO,_(DIFFIO_RX_R73n,_DIFFOUT_R73n)-PadL21)") (class "Default")
      (node (ref "D4") (pin "L21") (pinfunction "IO,_(DIFFIO_RX_R73n,_DIFFOUT_R73n)_L21") (pintype "bidirectional"))
    )
    (net (code "149") (name "unconnected-(D4F-IO,_(DIFFIO_RX_R73p,_DIFFOUT_R73p)-PadM21)") (class "Default")
      (node (ref "D4") (pin "M21") (pinfunction "IO,_(DIFFIO_RX_R73p,_DIFFOUT_R73p)_M21") (pintype "bidirectional"))
    )
    (net (code "150") (name "unconnected-(D4F-IO,_(DIFFIO_RX_R75n,_DIFFOUT_R75n,_DQ10R,_DQ3R)-PadH26)") (class "Default")
      (node (ref "D4") (pin "H26") (pinfunction "IO,_(DIFFIO_RX_R75n,_DIFFOUT_R75n,_DQ10R,_DQ3R)_H26") (pintype "bidirectional"))
    )
    (net (code "151") (name "unconnected-(D4F-IO,_(DIFFIO_RX_R75p,_DIFFOUT_R75p,_DQ10R,_DQ3R)-PadH25)") (class "Default")
      (node (ref "D4") (pin "H25") (pinfunction "IO,_(DIFFIO_RX_R75p,_DIFFOUT_R75p,_DQ10R,_DQ3R)_H25") (pintype "bidirectional"))
    )
    (net (code "152") (name "unconnected-(D4F-IO,_(DIFFIO_RX_R77n,_DIFFOUT_R77n,_DQSn10R,_DQ3R)-PadN20)") (class "Default")
      (node (ref "D4") (pin "N20") (pinfunction "IO,_(DIFFIO_RX_R77n,_DIFFOUT_R77n,_DQSn10R,_DQ3R)_N20") (pintype "bidirectional"))
    )
    (net (code "153") (name "unconnected-(D4F-IO,_(DIFFIO_RX_R77p,_DIFFOUT_R77p,_DQS10R,_DQ3R)-PadP20)") (class "Default")
      (node (ref "D4") (pin "P20") (pinfunction "IO,_(DIFFIO_RX_R77p,_DIFFOUT_R77p,_DQS10R,_DQ3R)_P20") (pintype "bidirectional"))
    )
    (net (code "154") (name "unconnected-(D4F-IO,_(DIFFIO_RX_R79n,_DIFFOUT_R79n,_DQ10R,_DQ3R)-PadJ23)") (class "Default")
      (node (ref "D4") (pin "J23") (pinfunction "IO,_(DIFFIO_RX_R79n,_DIFFOUT_R79n,_DQ10R,_DQ3R)_J23") (pintype "bidirectional"))
    )
    (net (code "155") (name "unconnected-(D4F-IO,_(DIFFIO_RX_R79p,_DIFFOUT_R79p,_DQ10R,_DQ3R)-PadJ22)") (class "Default")
      (node (ref "D4") (pin "J22") (pinfunction "IO,_(DIFFIO_RX_R79p,_DIFFOUT_R79p,_DQ10R,_DQ3R)_J22") (pintype "bidirectional"))
    )
    (net (code "156") (name "unconnected-(D4F-IO,_(DIFFIO_TX_R62n,_DIFFOUT_R62n,_DQ8R,_DQ2R)-PadG26)") (class "Default")
      (node (ref "D4") (pin "G26") (pinfunction "IO,_(DIFFIO_TX_R62n,_DIFFOUT_R62n,_DQ8R,_DQ2R)_G26") (pintype "bidirectional"))
    )
    (net (code "157") (name "unconnected-(D4F-IO,_(DIFFIO_TX_R62p,_DIFFOUT_R62p)-PadH27)") (class "Default")
      (node (ref "D4") (pin "H27") (pinfunction "IO,_(DIFFIO_TX_R62p,_DIFFOUT_R62p)_H27") (pintype "bidirectional"))
    )
    (net (code "158") (name "unconnected-(D4F-IO,_(DIFFIO_TX_R80p,_DIFFOUT_R80p,_DQ10R,_DQ3R)-PadH24)") (class "Default")
      (node (ref "D4") (pin "H24") (pinfunction "IO,_(DIFFIO_TX_R80p,_DIFFOUT_R80p,_DQ10R,_DQ3R)_H24") (pintype "bidirectional"))
    )
    (net (code "159") (name "unconnected-(D4F-IO,_CLK5n,_(DIFFIO_RX_R41n,_DIFFOUT_R41n)-PadR23)") (class "Default")
      (node (ref "D4") (pin "R23") (pinfunction "IO,_CLK5n,_(DIFFIO_RX_R41n,_DIFFOUT_R41n)_R23") (pintype "bidirectional"))
    )
    (net (code "160") (name "unconnected-(D4F-IO,_CLK5p,_(DIFFIO_RX_R41p,_DIFFOUT_R41p)-PadT23)") (class "Default")
      (node (ref "D4") (pin "T23") (pinfunction "IO,_CLK5p,_(DIFFIO_RX_R41p,_DIFFOUT_R41p)_T23") (pintype "bidirectional"))
    )
  )
)
